# Wired_Door_Bell.net
KiCad netlist of a schematic drawn in EAGLE
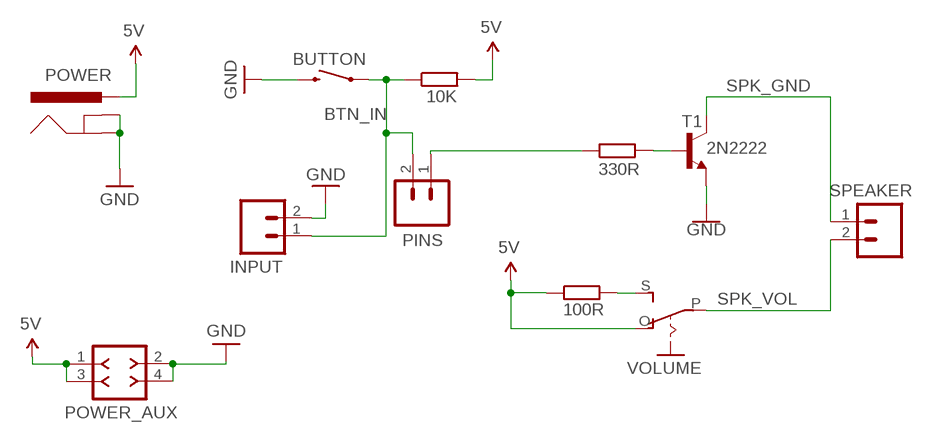
[diagram p0: schematic, sheet 1]

(export (version "E")
  (design (tool "Eeschema 10.0.6"))
  (components
    (comp (ref "10K")
      (value "10k")
      (footprint "eagle-import:0309V")
      (libsource (lib "eagle-import") (part "R-EU_0309/V"))
    )
    (comp (ref "100R")
      (value "100")
      (footprint "eagle-import:0309V")
      (libsource (lib "eagle-import") (part "R-EU_0309/V"))
    )
    (comp (ref "330R")
      (value "330")
      (footprint "eagle-import:0309V")
      (libsource (lib "eagle-import") (part "R-EU_0309/V"))
    )
    (comp (ref "BUTTON")
      (value "MOMENTARY-SWITCH-SPST-PTH-6.0MM")
      (footprint "eagle-import:TACTILE_SWITCH_PTH_6.0MM")
      (libsource (lib "eagle-import") (part "MOMENTARY-SWITCH-SPST-PTH-6.0MM"))
    )
    (comp (ref "INPUT")
      (value "CONN_02")
      (footprint "eagle-import:1X02")
      (libsource (lib "eagle-import") (part "CONN_02"))
    )
    (comp (ref "PINS")
      (value "CONN_02")
      (footprint "eagle-import:1X02")
      (libsource (lib "eagle-import") (part "CONN_02"))
    )
    (comp (ref "POWER")
      (value "POWER_JACK")
      (footprint "eagle-import:POWER_JACK_PTH")
      (libsource (lib "eagle-import") (part "POWER_JACK"))
    )
    (comp (ref "POWER_AUX")
      (value "F-2X02-DIL-100")
      (footprint "eagle-import:DIL-100-2X02")
      (libsource (lib "eagle-import") (part "F-2X02-DIL-100"))
    )
    (comp (ref "SPEAKER")
      (value "CONN_02")
      (footprint "eagle-import:1X02")
      (libsource (lib "eagle-import") (part "CONN_02"))
    )
    (comp (ref "T1")
      (value "2N2222")
      (footprint "eagle-import:TO92-EBC-OVAL")
      (libsource (lib "eagle-import") (part "2N2222"))
    )
    (comp (ref "VOLUME")
      (value "EG1218S")
      (footprint "eagle-import:EG1218")
      (libsource (lib "eagle-import") (part "EG1218S"))
    )
  )
  (nets
    (net (code "1") (name "/BTN_IN") (class "Default")
      (node (ref "10K") (pin "1") (pinfunction "1_1") (pintype "passive"))
      (node (ref "BUTTON") (pin "1") (pinfunction "1_1") (pintype "passive"))
      (node (ref "INPUT") (pin "1") (pinfunction "1_1") (pintype "passive"))
      (node (ref "PINS") (pin "2") (pinfunction "2_2") (pintype "passive"))
    )
    (net (code "2") (name "/SPK_GND") (class "Default")
      (node (ref "SPEAKER") (pin "1") (pinfunction "1_1") (pintype "passive"))
      (node (ref "T1") (pin "C") (pinfunction "C_C") (pintype "passive"))
    )
    (net (code "3") (name "/SPK_VOL") (class "Default")
      (node (ref "SPEAKER") (pin "2") (pinfunction "2_2") (pintype "passive"))
      (node (ref "VOLUME") (pin "P") (pinfunction "P_P") (pintype "passive"))
    )
    (net (code "4") (name "5V") (class "Default")
      (node (ref "100R") (pin "1") (pinfunction "1_1") (pintype "passive"))
      (node (ref "10K") (pin "2") (pinfunction "2_2") (pintype "passive"))
      (node (ref "POWER") (pin "PWR") (pinfunction "PWR_PWR") (pintype "bidirectional"))
      (node (ref "POWER_AUX") (pin "1") (pinfunction "1_1") (pintype "passive"))
      (node (ref "POWER_AUX") (pin "3") (pinfunction "3_3") (pintype "passive"))
      (node (ref "VOLUME") (pin "O") (pinfunction "O_O") (pintype "passive"))
    )
    (net (code "5") (name "GND") (class "Default")
      (node (ref "BUTTON") (pin "3") (pinfunction "2_3") (pintype "passive"))
      (node (ref "INPUT") (pin "2") (pinfunction "2_2") (pintype "passive"))
      (node (ref "POWER") (pin "GND") (pinfunction "GND_GND") (pintype "bidirectional"))
      (node (ref "POWER") (pin "GNDBREAK") (pinfunction "GNDBREAK_GNDBREAK") (pintype "bidirectional"))
      (node (ref "POWER_AUX") (pin "2") (pinfunction "2_2") (pintype "passive"))
      (node (ref "POWER_AUX") (pin "4") (pinfunction "4_4") (pintype "passive"))
      (node (ref "T1") (pin "E") (pinfunction "E_E") (pintype "passive"))
    )
    (net (code "6") (name "Net-(100R-Pad2)") (class "Default")
      (node (ref "100R") (pin "2") (pinfunction "2_2") (pintype "passive"))
      (node (ref "VOLUME") (pin "S") (pinfunction "S_S") (pintype "passive"))
    )
    (net (code "7") (name "Net-(330R-Pad1)") (class "Default")
      (node (ref "330R") (pin "1") (pinfunction "1_1") (pintype "passive"))
      (node (ref "PINS") (pin "1") (pinfunction "1_1") (pintype "passive"))
    )
    (net (code "8") (name "Net-(330R-Pad2)") (class "Default")
      (node (ref "330R") (pin "2") (pinfunction "2_2") (pintype "passive"))
      (node (ref "T1") (pin "B") (pinfunction "B_B") (pintype "passive"))
    )
  )
)
